# Tricorder-BoosterPack.net
KiCad netlist of a schematic drawn in EAGLE
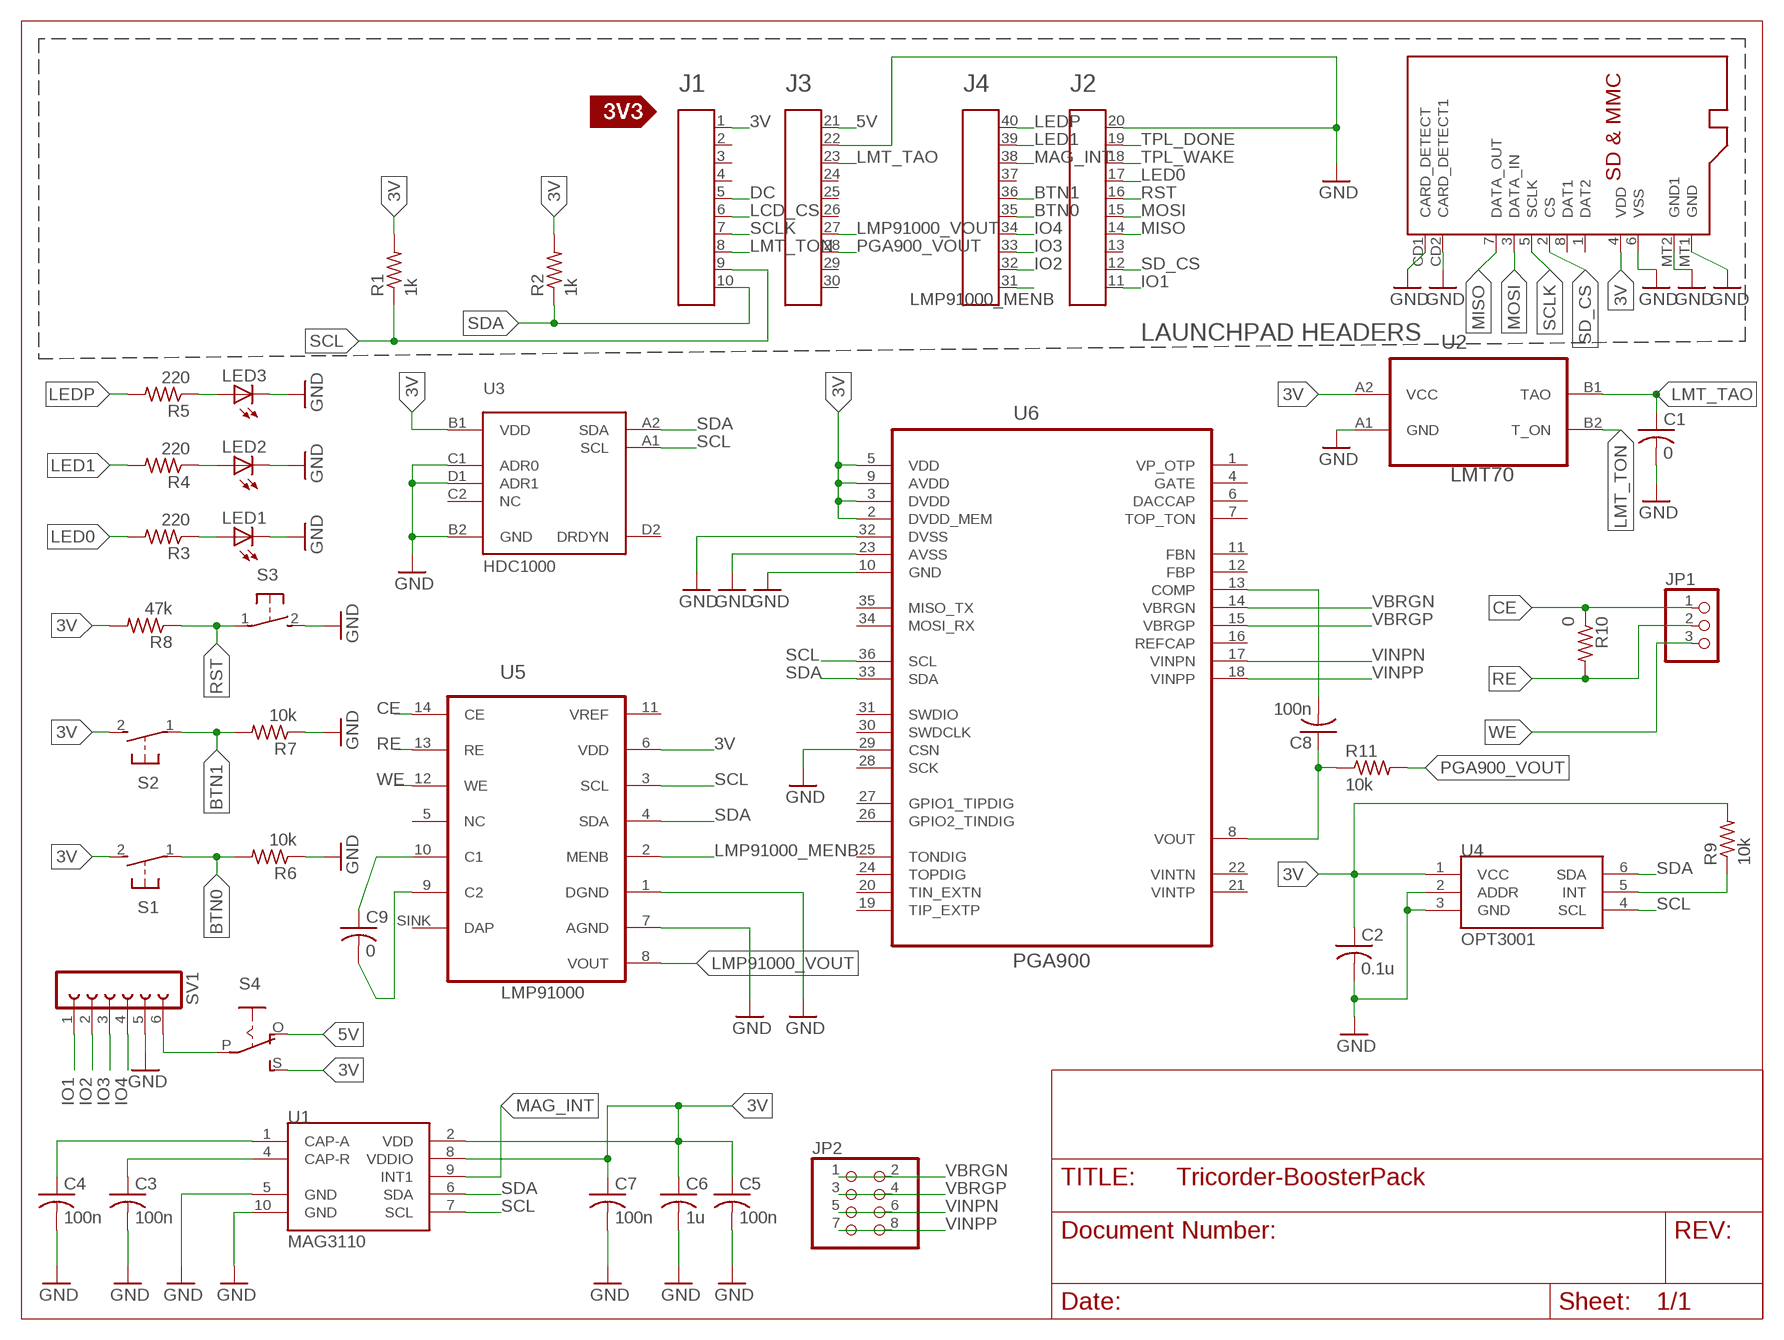
[diagram p0: schematic, sheet 1]

(export (version "E")
  (design (tool "Eeschema 10.0.6"))
  (components
    (comp (ref "A1")
      (value "HEADER4X10-BOOSTERPACK")
      (footprint "eagle-import:4X10-BOOSTERPACK")
      (libsource (lib "eagle-import") (part "HEADER4X10-BOOSTERPACK"))
    )
    (comp (ref "C1")
      (value "0")
      (footprint "eagle-import:C0603")
      (libsource (lib "eagle-import") (part "C-USC0603"))
    )
    (comp (ref "C2")
      (value "0.1u")
      (footprint "eagle-import:C0603")
      (libsource (lib "eagle-import") (part "C-USC0603"))
    )
    (comp (ref "C3")
      (value "100n")
      (footprint "eagle-import:C0603")
      (libsource (lib "eagle-import") (part "C-USC0603"))
    )
    (comp (ref "C4")
      (value "100n")
      (footprint "eagle-import:C0603")
      (libsource (lib "eagle-import") (part "C-USC0603"))
    )
    (comp (ref "C5")
      (value "100n")
      (footprint "eagle-import:C0603")
      (libsource (lib "eagle-import") (part "C-USC0603"))
    )
    (comp (ref "C6")
      (value "1u")
      (footprint "eagle-import:C0603")
      (libsource (lib "eagle-import") (part "C-USC0603"))
    )
    (comp (ref "C7")
      (value "100n")
      (footprint "eagle-import:C0603")
      (libsource (lib "eagle-import") (part "C-USC0603"))
    )
    (comp (ref "C8")
      (value "100n")
      (footprint "eagle-import:C0603")
      (libsource (lib "eagle-import") (part "C-USC0603"))
    )
    (comp (ref "C9")
      (value "0")
      (footprint "eagle-import:C0603")
      (libsource (lib "eagle-import") (part "C-USC0603"))
    )
    (comp (ref "JP1")
      (value "PINHD-1X3CB")
      (footprint "eagle-import:1X03-CLEANBIG")
      (libsource (lib "eagle-import") (part "PINHD-1X3CB"))
    )
    (comp (ref "JP2")
      (value "PINHD-2X4")
      (footprint "eagle-import:2X04")
      (libsource (lib "eagle-import") (part "PINHD-2X4"))
    )
    (comp (ref "LED1")
      (value "LEDCHIPLED_0603")
      (footprint "eagle-import:CHIPLED_0603")
      (libsource (lib "eagle-import") (part "LEDCHIPLED_0603"))
    )
    (comp (ref "LED2")
      (value "LEDCHIPLED_0603")
      (footprint "eagle-import:CHIPLED_0603")
      (libsource (lib "eagle-import") (part "LEDCHIPLED_0603"))
    )
    (comp (ref "LED3")
      (value "LEDCHIPLED_0603")
      (footprint "eagle-import:CHIPLED_0603")
      (libsource (lib "eagle-import") (part "LEDCHIPLED_0603"))
    )
    (comp (ref "R1")
      (value "1k")
      (footprint "eagle-import:R0603")
      (libsource (lib "eagle-import") (part "R-US_R0603"))
    )
    (comp (ref "R2")
      (value "1k")
      (footprint "eagle-import:R0603")
      (libsource (lib "eagle-import") (part "R-US_R0603"))
    )
    (comp (ref "R3")
      (value "220")
      (footprint "eagle-import:R0603")
      (libsource (lib "eagle-import") (part "R-US_R0603"))
    )
    (comp (ref "R4")
      (value "220")
      (footprint "eagle-import:R0603")
      (libsource (lib "eagle-import") (part "R-US_R0603"))
    )
    (comp (ref "R5")
      (value "220")
      (footprint "eagle-import:R0603")
      (libsource (lib "eagle-import") (part "R-US_R0603"))
    )
    (comp (ref "R6")
      (value "10k")
      (footprint "eagle-import:R0603")
      (libsource (lib "eagle-import") (part "R-US_R0603"))
    )
    (comp (ref "R7")
      (value "10k")
      (footprint "eagle-import:R0603")
      (libsource (lib "eagle-import") (part "R-US_R0603"))
    )
    (comp (ref "R8")
      (value "47k")
      (footprint "eagle-import:R0603")
      (libsource (lib "eagle-import") (part "R-US_R0603"))
    )
    (comp (ref "R9")
      (value "10k")
      (footprint "eagle-import:R0603")
      (libsource (lib "eagle-import") (part "R-US_R0603"))
    )
    (comp (ref "R10")
      (value "0")
      (footprint "eagle-import:R0603")
      (libsource (lib "eagle-import") (part "R-US_R0603"))
    )
    (comp (ref "R11")
      (value "10k")
      (footprint "eagle-import:R0603")
      (libsource (lib "eagle-import") (part "R-US_R0603"))
    )
    (comp (ref "S1")
      (value "31-XX")
      (footprint "eagle-import:B3F-31XX")
      (libsource (lib "eagle-import") (part "31-XX"))
    )
    (comp (ref "S2")
      (value "31-XX")
      (footprint "eagle-import:B3F-31XX")
      (libsource (lib "eagle-import") (part "31-XX"))
    )
    (comp (ref "S3")
      (value "31-XX")
      (footprint "eagle-import:B3F-31XX")
      (libsource (lib "eagle-import") (part "31-XX"))
    )
    (comp (ref "S4")
      (value "EG1218S")
      (footprint "eagle-import:EG1218")
      (libsource (lib "eagle-import") (part "EG1218S"))
    )
    (comp (ref "SV1")
      (value "FE06-1")
      (footprint "eagle-import:FE06")
      (libsource (lib "eagle-import") (part "FE06-1"))
    )
    (comp (ref "U$3")
      (value "SILK_3V3_TAG")
      (footprint "eagle-import:SILK_3V3_TAG")
      (libsource (lib "eagle-import") (part "SILK_3V3_TAG"))
    )
    (comp (ref "U1")
      (value "MAG3110")
      (footprint "eagle-import:DFN-10")
      (libsource (lib "eagle-import") (part "MAG3110"))
    )
    (comp (ref "U2")
      (value "LMT70LMT70")
      (footprint "eagle-import:BGA4C40P2X2_77X77X50")
      (fields (field (name "MPN") "LMT70"))
      (libsource (lib "eagle-import") (part "LMT70LMT70"))
    )
    (comp (ref "U3")
      (value "HDC1000")
      (footprint "eagle-import:DSBGA_8_YPA")
      (libsource (lib "eagle-import") (part "HDC1000"))
    )
    (comp (ref "U4")
      (value "OPT3001")
      (footprint "eagle-import:SOT23-6")
      (libsource (lib "eagle-import") (part "OPT3001"))
    )
    (comp (ref "U5")
      (value "LMP91000")
      (footprint "eagle-import:WFDFN-14")
      (fields (field (name "DIGIKEY") "LMP91000SDE/NOPBCT-ND") (field (name "DIGIKEY_1") "LMP91000"))
      (libsource (lib "eagle-import") (part "LMP91000"))
    )
    (comp (ref "U6")
      (value "PGA900")
      (footprint "eagle-import:QFN50P600X600X90-37N")
      (libsource (lib "eagle-import") (part "PGA900"))
    )
    (comp (ref "U7")
      (value "MICROSD")
      (footprint "eagle-import:MICROSD")
      (libsource (lib "eagle-import") (part "MICROSD"))
    )
  )
  (nets
    (net (code "1") (name "/DC") (class "Default")
      (node (ref "A1") (pin "5") (pinfunction "P$5_5") (pintype "bidirectional"))
    )
    (net (code "2") (name "/IO1") (class "Default")
      (node (ref "A1") (pin "11") (pinfunction "P$11_11") (pintype "bidirectional"))
      (node (ref "SV1") (pin "1") (pinfunction "1_1") (pintype "passive"))
    )
    (net (code "3") (name "/IO2") (class "Default")
      (node (ref "A1") (pin "32") (pinfunction "P$32_32") (pintype "bidirectional"))
      (node (ref "SV1") (pin "2") (pinfunction "2_2") (pintype "passive"))
    )
    (net (code "4") (name "/IO3") (class "Default")
      (node (ref "A1") (pin "33") (pinfunction "P$33_33") (pintype "bidirectional"))
      (node (ref "SV1") (pin "3") (pinfunction "3_3") (pintype "passive"))
    )
    (net (code "5") (name "/IO4") (class "Default")
      (node (ref "A1") (pin "34") (pinfunction "P$34_34") (pintype "bidirectional"))
      (node (ref "SV1") (pin "4") (pinfunction "4_4") (pintype "passive"))
    )
    (net (code "6") (name "/LCD_CS") (class "Default")
      (node (ref "A1") (pin "6") (pinfunction "P$6_6") (pintype "bidirectional"))
    )
    (net (code "7") (name "/LMP91000_MENB") (class "Default")
      (node (ref "A1") (pin "31") (pinfunction "P$31_31") (pintype "bidirectional"))
      (node (ref "U5") (pin "2") (pinfunction "MENB_2") (pintype "passive"))
    )
    (net (code "8") (name "/TPL_DONE") (class "Default")
      (node (ref "A1") (pin "19") (pinfunction "P$19_19") (pintype "bidirectional"))
    )
    (net (code "9") (name "/TPL_WAKE") (class "Default")
      (node (ref "A1") (pin "18") (pinfunction "P$18_18") (pintype "bidirectional"))
    )
    (net (code "10") (name "/VBRGN") (class "Default")
      (node (ref "JP2") (pin "1") (pinfunction "1_1") (pintype "passive"))
      (node (ref "JP2") (pin "2") (pinfunction "2_2") (pintype "passive"))
      (node (ref "U6") (pin "14") (pinfunction "VBRGN_14") (pintype "bidirectional"))
    )
    (net (code "11") (name "/VBRGP") (class "Default")
      (node (ref "JP2") (pin "3") (pinfunction "3_3") (pintype "passive"))
      (node (ref "JP2") (pin "4") (pinfunction "4_4") (pintype "passive"))
      (node (ref "U6") (pin "15") (pinfunction "VBRGP_15") (pintype "bidirectional"))
    )
    (net (code "12") (name "/VINPN") (class "Default")
      (node (ref "JP2") (pin "5") (pinfunction "5_5") (pintype "passive"))
      (node (ref "JP2") (pin "6") (pinfunction "6_6") (pintype "passive"))
      (node (ref "U6") (pin "17") (pinfunction "VINPN_17") (pintype "bidirectional"))
    )
    (net (code "13") (name "/VINPP") (class "Default")
      (node (ref "JP2") (pin "7") (pinfunction "7_7") (pintype "passive"))
      (node (ref "JP2") (pin "8") (pinfunction "8_8") (pintype "passive"))
      (node (ref "U6") (pin "18") (pinfunction "VINPP_18") (pintype "bidirectional"))
    )
    (net (code "14") (name "/VREF") (class "Default")
      (node (ref "U5") (pin "11") (pinfunction "VREF_11") (pintype "power_in"))
    )
    (net (code "15") (name "3V") (class "Default")
      (node (ref "A1") (pin "1") (pinfunction "P$1_1") (pintype "bidirectional"))
      (node (ref "C2") (pin "1") (pinfunction "1_1") (pintype "passive"))
      (node (ref "C5") (pin "1") (pinfunction "1_1") (pintype "passive"))
      (node (ref "C6") (pin "1") (pinfunction "1_1") (pintype "passive"))
      (node (ref "C7") (pin "1") (pinfunction "1_1") (pintype "passive"))
      (node (ref "R1") (pin "2") (pinfunction "2_2") (pintype "passive"))
      (node (ref "R2") (pin "2") (pinfunction "2_2") (pintype "passive"))
      (node (ref "R8") (pin "2") (pinfunction "2_2") (pintype "passive"))
      (node (ref "R9") (pin "2") (pinfunction "2_2") (pintype "passive"))
      (node (ref "S1") (pin "2") (pinfunction "S_2") (pintype "passive"))
      (node (ref "S2") (pin "2") (pinfunction "S_2") (pintype "passive"))
      (node (ref "S4") (pin "S") (pinfunction "S_S") (pintype "passive"))
      (node (ref "U1") (pin "2") (pinfunction "VDD_2") (pintype "bidirectional"))
      (node (ref "U1") (pin "8") (pinfunction "VDDIO_8") (pintype "bidirectional"))
      (node (ref "U3") (pin "B1") (pinfunction "VDD_B1") (pintype "power_in"))
      (node (ref "U4") (pin "1") (pinfunction "VCC_1") (pintype "power_in"))
      (node (ref "U5") (pin "6") (pinfunction "VDD_6") (pintype "power_in"))
      (node (ref "U6") (pin "2") (pinfunction "DVDD_MEM_2") (pintype "power_in"))
      (node (ref "U6") (pin "3") (pinfunction "DVDD_3") (pintype "power_in"))
      (node (ref "U6") (pin "5") (pinfunction "VDD_5") (pintype "power_in"))
      (node (ref "U6") (pin "9") (pinfunction "AVDD_9") (pintype "power_in"))
      (node (ref "U7") (pin "4") (pinfunction "VDD_4") (pintype "power_in"))
    )
    (net (code "16") (name "5V") (class "Default")
      (node (ref "A1") (pin "21") (pinfunction "P$21_21") (pintype "bidirectional"))
      (node (ref "S4") (pin "O") (pinfunction "O_O") (pintype "passive"))
    )
    (net (code "17") (name "BTN0") (class "Default")
      (node (ref "A1") (pin "35") (pinfunction "P$35_35") (pintype "bidirectional"))
      (node (ref "R6") (pin "2") (pinfunction "2_2") (pintype "passive"))
      (node (ref "S1") (pin "1") (pinfunction "P_1") (pintype "passive"))
    )
    (net (code "18") (name "BTN1") (class "Default")
      (node (ref "A1") (pin "36") (pinfunction "P$36_36") (pintype "bidirectional"))
      (node (ref "R7") (pin "2") (pinfunction "2_2") (pintype "passive"))
      (node (ref "S2") (pin "1") (pinfunction "P_1") (pintype "passive"))
    )
    (net (code "19") (name "CE") (class "Default")
      (node (ref "JP1") (pin "1") (pinfunction "1_1") (pintype "passive"))
      (node (ref "R10") (pin "1") (pinfunction "1_1") (pintype "passive"))
      (node (ref "U5") (pin "14") (pinfunction "CE_14") (pintype "bidirectional"))
    )
    (net (code "20") (name "GND") (class "Default")
      (node (ref "A1") (pin "20") (pinfunction "P$20_20") (pintype "bidirectional"))
      (node (ref "A1") (pin "22") (pinfunction "P$22_22") (pintype "bidirectional"))
      (node (ref "C1") (pin "2") (pinfunction "2_2") (pintype "passive"))
      (node (ref "C2") (pin "2") (pinfunction "2_2") (pintype "passive"))
      (node (ref "C3") (pin "2") (pinfunction "2_2") (pintype "passive"))
      (node (ref "C4") (pin "2") (pinfunction "2_2") (pintype "passive"))
      (node (ref "C5") (pin "2") (pinfunction "2_2") (pintype "passive"))
      (node (ref "C6") (pin "2") (pinfunction "2_2") (pintype "passive"))
      (node (ref "C7") (pin "2") (pinfunction "2_2") (pintype "passive"))
      (node (ref "LED1") (pin "C") (pinfunction "C_C") (pintype "passive"))
      (node (ref "LED2") (pin "C") (pinfunction "C_C") (pintype "passive"))
      (node (ref "LED3") (pin "C") (pinfunction "C_C") (pintype "passive"))
      (node (ref "R6") (pin "1") (pinfunction "1_1") (pintype "passive"))
      (node (ref "R7") (pin "1") (pinfunction "1_1") (pintype "passive"))
      (node (ref "S3") (pin "2") (pinfunction "S_2") (pintype "passive"))
      (node (ref "SV1") (pin "5") (pinfunction "5_5") (pintype "passive"))
      (node (ref "U1") (pin "10") (pinfunction "GND_10") (pintype "bidirectional"))
      (node (ref "U1") (pin "5") (pinfunction "GND_5") (pintype "bidirectional"))
      (node (ref "U2") (pin "A1") (pinfunction "GND_A1") (pintype "passive"))
      (node (ref "U3") (pin "B2") (pinfunction "GND_B2") (pintype "power_in"))
      (node (ref "U3") (pin "C1") (pinfunction "ADR0_C1") (pintype "input"))
      (node (ref "U3") (pin "D1") (pinfunction "ADR1_D1") (pintype "input"))
      (node (ref "U4") (pin "2") (pinfunction "ADDR_2") (pintype "input"))
      (node (ref "U4") (pin "3") (pinfunction "GND_3") (pintype "power_in"))
      (node (ref "U5") (pin "1") (pinfunction "DGND_1") (pintype "passive"))
      (node (ref "U5") (pin "7") (pinfunction "AGND_7") (pintype "passive"))
      (node (ref "U6") (pin "10") (pinfunction "GND_10") (pintype "power_in"))
      (node (ref "U6") (pin "23") (pinfunction "AVSS_23") (pintype "power_in"))
      (node (ref "U6") (pin "29") (pinfunction "CSN_29") (pintype "output"))
      (node (ref "U6") (pin "32") (pinfunction "DVSS_32") (pintype "power_in"))
      (node (ref "U7") (pin "6") (pinfunction "VSS_6") (pintype "power_in"))
      (node (ref "U7") (pin "CD1") (pinfunction "CARD_DETECT_CD1") (pintype "passive"))
      (node (ref "U7") (pin "CD2") (pinfunction "CARD_DETECT1_CD2") (pintype "passive"))
      (node (ref "U7") (pin "MT1") (pinfunction "GND_MT1") (pintype "power_in"))
      (node (ref "U7") (pin "MT2") (pinfunction "GND1_MT2") (pintype "power_in"))
    )
    (net (code "21") (name "LED0") (class "Default")
      (node (ref "A1") (pin "17") (pinfunction "P$17_17") (pintype "bidirectional"))
      (node (ref "R3") (pin "2") (pinfunction "2_2") (pintype "passive"))
    )
    (net (code "22") (name "LED1") (class "Default")
      (node (ref "A1") (pin "39") (pinfunction "P$39_39") (pintype "bidirectional"))
      (node (ref "R4") (pin "2") (pinfunction "2_2") (pintype "passive"))
    )
    (net (code "23") (name "LEDP") (class "Default")
      (node (ref "A1") (pin "40") (pinfunction "P$40_40") (pintype "bidirectional"))
      (node (ref "R5") (pin "2") (pinfunction "2_2") (pintype "passive"))
    )
    (net (code "24") (name "LMP91000_VOUT") (class "Default")
      (node (ref "A1") (pin "27") (pinfunction "P$27_27") (pintype "bidirectional"))
      (node (ref "U5") (pin "8") (pinfunction "VOUT_8") (pintype "passive"))
    )
    (net (code "25") (name "LMT_TAO") (class "Default")
      (node (ref "A1") (pin "23") (pinfunction "P$23_23") (pintype "bidirectional"))
      (node (ref "C1") (pin "1") (pinfunction "1_1") (pintype "passive"))
      (node (ref "U2") (pin "B1") (pinfunction "TAO_B1") (pintype "output"))
    )
    (net (code "26") (name "LMT_TON") (class "Default")
      (node (ref "A1") (pin "8") (pinfunction "P$8_8") (pintype "bidirectional"))
      (node (ref "U2") (pin "B2") (pinfunction "T_ON_B2") (pintype "input"))
    )
    (net (code "27") (name "MAG_INT") (class "Default")
      (node (ref "A1") (pin "38") (pinfunction "P$38_38") (pintype "bidirectional"))
      (node (ref "U1") (pin "9") (pinfunction "INT1_9") (pintype "bidirectional"))
    )
    (net (code "28") (name "MISO") (class "Default")
      (node (ref "A1") (pin "14") (pinfunction "P$14_14") (pintype "bidirectional"))
      (node (ref "U7") (pin "7") (pinfunction "DATA_OUT_7") (pintype "output"))
    )
    (net (code "29") (name "MOSI") (class "Default")
      (node (ref "A1") (pin "15") (pinfunction "P$15_15") (pintype "bidirectional"))
      (node (ref "U7") (pin "3") (pinfunction "DATA_IN_3") (pintype "input"))
    )
    (net (code "30") (name "Net-(LED1-PadA)") (class "Default")
      (node (ref "LED1") (pin "A") (pinfunction "A_A") (pintype "passive"))
      (node (ref "R3") (pin "1") (pinfunction "1_1") (pintype "passive"))
    )
    (net (code "31") (name "Net-(LED2-PadA)") (class "Default")
      (node (ref "LED2") (pin "A") (pinfunction "A_A") (pintype "passive"))
      (node (ref "R4") (pin "1") (pinfunction "1_1") (pintype "passive"))
    )
    (net (code "32") (name "Net-(LED3-PadA)") (class "Default")
      (node (ref "LED3") (pin "A") (pinfunction "A_A") (pintype "passive"))
      (node (ref "R5") (pin "1") (pinfunction "1_1") (pintype "passive"))
    )
    (net (code "33") (name "Net-(S4-PadP)") (class "Default")
      (node (ref "S4") (pin "P") (pinfunction "P_P") (pintype "passive"))
      (node (ref "SV1") (pin "6") (pinfunction "6_6") (pintype "passive"))
    )
    (net (code "34") (name "Net-(U1-CAP-A)") (class "Default")
      (node (ref "C4") (pin "1") (pinfunction "1_1") (pintype "passive"))
      (node (ref "U1") (pin "1") (pinfunction "CAP-A_1") (pintype "bidirectional"))
    )
    (net (code "35") (name "Net-(U1-CAP-R)") (class "Default")
      (node (ref "C3") (pin "1") (pinfunction "1_1") (pintype "passive"))
      (node (ref "U1") (pin "4") (pinfunction "CAP-R_4") (pintype "bidirectional"))
    )
    (net (code "36") (name "Net-(U4-INT)") (class "Default")
      (node (ref "R9") (pin "1") (pinfunction "1_1") (pintype "passive"))
      (node (ref "U4") (pin "5") (pinfunction "INT_5") (pintype "output"))
    )
    (net (code "37") (name "Net-(U5-C1)") (class "Default")
      (node (ref "C9") (pin "1") (pinfunction "1_1") (pintype "passive"))
      (node (ref "U5") (pin "10") (pinfunction "C1_10") (pintype "passive"))
    )
    (net (code "38") (name "Net-(U5-C2)") (class "Default")
      (node (ref "C9") (pin "2") (pinfunction "2_2") (pintype "passive"))
      (node (ref "U5") (pin "9") (pinfunction "C2_9") (pintype "passive"))
    )
    (net (code "39") (name "Net-(U6-COMP)") (class "Default")
      (node (ref "C8") (pin "2") (pinfunction "2_2") (pintype "passive"))
      (node (ref "U6") (pin "13") (pinfunction "COMP_13") (pintype "bidirectional"))
    )
    (net (code "40") (name "Net-(U6-VOUT)") (class "Default")
      (node (ref "C8") (pin "1") (pinfunction "1_1") (pintype "passive"))
      (node (ref "R11") (pin "1") (pinfunction "1_1") (pintype "passive"))
      (node (ref "U6") (pin "8") (pinfunction "VOUT_8") (pintype "bidirectional"))
    )
    (net (code "41") (name "PGA900_VOUT") (class "Default")
      (node (ref "A1") (pin "28") (pinfunction "P$28_28") (pintype "bidirectional"))
      (node (ref "R11") (pin "2") (pinfunction "2_2") (pintype "passive"))
    )
    (net (code "42") (name "RE") (class "Default")
      (node (ref "JP1") (pin "2") (pinfunction "2_2") (pintype "passive"))
      (node (ref "R10") (pin "2") (pinfunction "2_2") (pintype "passive"))
      (node (ref "U5") (pin "13") (pinfunction "RE_13") (pintype "bidirectional"))
    )
    (net (code "43") (name "RST") (class "Default")
      (node (ref "A1") (pin "16") (pinfunction "P$16_16") (pintype "bidirectional"))
      (node (ref "R8") (pin "1") (pinfunction "1_1") (pintype "passive"))
      (node (ref "S3") (pin "1") (pinfunction "P_1") (pintype "passive"))
    )
    (net (code "44") (name "SCL") (class "Default")
      (node (ref "A1") (pin "9") (pinfunction "P$9_9") (pintype "bidirectional"))
      (node (ref "R1") (pin "1") (pinfunction "1_1") (pintype "passive"))
      (node (ref "U1") (pin "7") (pinfunction "SCL_7") (pintype "bidirectional"))
      (node (ref "U3") (pin "A1") (pinfunction "SCL_A1") (pintype "input"))
      (node (ref "U4") (pin "4") (pinfunction "SCL_4") (pintype "input"))
      (node (ref "U5") (pin "3") (pinfunction "SCL_3") (pintype "bidirectional"))
      (node (ref "U6") (pin "36") (pinfunction "SCL_36") (pintype "bidirectional"))
    )
    (net (code "45") (name "SCLK") (class "Default")
      (node (ref "A1") (pin "7") (pinfunction "P$7_7") (pintype "bidirectional"))
      (node (ref "U7") (pin "5") (pinfunction "SCLK_5") (pintype "input"))
    )
    (net (code "46") (name "SDA") (class "Default")
      (node (ref "A1") (pin "10") (pinfunction "P$10_10") (pintype "bidirectional"))
      (node (ref "R2") (pin "1") (pinfunction "1_1") (pintype "passive"))
      (node (ref "U1") (pin "6") (pinfunction "SDA_6") (pintype "bidirectional"))
      (node (ref "U3") (pin "A2") (pinfunction "SDA_A2") (pintype "bidirectional"))
      (node (ref "U4") (pin "6") (pinfunction "SDA_6") (pintype "input"))
      (node (ref "U5") (pin "4") (pinfunction "SDA_4") (pintype "passive"))
      (node (ref "U6") (pin "33") (pinfunction "SDA_33") (pintype "bidirectional"))
    )
    (net (code "47") (name "SD_CS") (class "Default")
      (node (ref "A1") (pin "12") (pinfunction "P$12_12") (pintype "bidirectional"))
      (node (ref "U7") (pin "2") (pinfunction "CS_2") (pintype "input"))
    )
    (net (code "48") (name "WE") (class "Default")
      (node (ref "JP1") (pin "3") (pinfunction "3_3") (pintype "passive"))
      (node (ref "U5") (pin "12") (pinfunction "WE_12") (pintype "bidirectional"))
    )
    (net (code "49") (name "unconnected-(A1-P$2-Pad2)") (class "Default")
      (node (ref "A1") (pin "2") (pinfunction "P$2_2") (pintype "bidirectional"))
    )
    (net (code "50") (name "unconnected-(A1-P$3-Pad3)") (class "Default")
      (node (ref "A1") (pin "3") (pinfunction "P$3_3") (pintype "bidirectional"))
    )
    (net (code "51") (name "unconnected-(A1-P$4-Pad4)") (class "Default")
      (node (ref "A1") (pin "4") (pinfunction "P$4_4") (pintype "bidirectional"))
    )
    (net (code "52") (name "unconnected-(A1-P$13-Pad13)") (class "Default")
      (node (ref "A1") (pin "13") (pinfunction "P$13_13") (pintype "bidirectional"))
    )
    (net (code "53") (name "unconnected-(A1-P$24-Pad24)") (class "Default")
      (node (ref "A1") (pin "24") (pinfunction "P$24_24") (pintype "bidirectional"))
    )
    (net (code "54") (name "unconnected-(A1-P$25-Pad25)") (class "Default")
      (node (ref "A1") (pin "25") (pinfunction "P$25_25") (pintype "bidirectional"))
    )
    (net (code "55") (name "unconnected-(A1-P$26-Pad26)") (class "Default")
      (node (ref "A1") (pin "26") (pinfunction "P$26_26") (pintype "bidirectional"))
    )
    (net (code "56") (name "unconnected-(A1-P$29-Pad29)") (class "Default")
      (node (ref "A1") (pin "29") (pinfunction "P$29_29") (pintype "bidirectional"))
    )
    (net (code "57") (name "unconnected-(A1-P$30-Pad30)") (class "Default")
      (node (ref "A1") (pin "30") (pinfunction "P$30_30") (pintype "bidirectional"))
    )
    (net (code "58") (name "unconnected-(A1-P$37-Pad37)") (class "Default")
      (node (ref "A1") (pin "37") (pinfunction "P$37_37") (pintype "bidirectional"))
    )
    (net (code "59") (name "unconnected-(U2-VCC-PadA2)") (class "Default")
      (node (ref "U2") (pin "A2") (pinfunction "VCC_A2") (pintype "power_in"))
    )
    (net (code "60") (name "unconnected-(U3-DRDYN-PadD2)") (class "Default")
      (node (ref "U3") (pin "D2") (pinfunction "DRDYN_D2") (pintype "output"))
    )
    (net (code "61") (name "unconnected-(U3-NC-PadC2)") (class "Default")
      (node (ref "U3") (pin "C2") (pinfunction "NC_C2") (pintype "no_connect"))
    )
    (net (code "62") (name "unconnected-(U5-DAP-PadSINK)") (class "Default")
      (node (ref "U5") (pin "SINK") (pinfunction "DAP_SINK") (pintype "passive"))
    )
    (net (code "63") (name "unconnected-(U5-NC-Pad5)") (class "Default")
      (node (ref "U5") (pin "5") (pinfunction "NC_5") (pintype "passive"))
    )
    (net (code "64") (name "unconnected-(U6-DACCAP-Pad6)") (class "Default")
      (node (ref "U6") (pin "6") (pinfunction "DACCAP_6") (pintype "bidirectional"))
    )
    (net (code "65") (name "unconnected-(U6-FBN-Pad11)") (class "Default")
      (node (ref "U6") (pin "11") (pinfunction "FBN_11") (pintype "bidirectional"))
    )
    (net (code "66") (name "unconnected-(U6-FBP-Pad12)") (class "Default")
      (node (ref "U6") (pin "12") (pinfunction "FBP_12") (pintype "bidirectional"))
    )
    (net (code "67") (name "unconnected-(U6-GATE-Pad4)") (class "Default")
      (node (ref "U6") (pin "4") (pinfunction "GATE_4") (pintype "bidirectional"))
    )
    (net (code "68") (name "unconnected-(U6-GPIO1_TIPDIG-Pad27)") (class "Default")
      (node (ref "U6") (pin "27") (pinfunction "GPIO1_TIPDIG_27") (pintype "bidirectional"))
    )
    (net (code "69") (name "unconnected-(U6-GPIO2_TINDIG-Pad26)") (class "Default")
      (node (ref "U6") (pin "26") (pinfunction "GPIO2_TINDIG_26") (pintype "bidirectional"))
    )
    (net (code "70") (name "unconnected-(U6-MISO_TX-Pad35)") (class "Default")
      (node (ref "U6") (pin "35") (pinfunction "MISO_TX_35") (pintype "output"))
    )
    (net (code "71") (name "unconnected-(U6-MOSI_RX-Pad34)") (class "Default")
      (node (ref "U6") (pin "34") (pinfunction "MOSI_RX_34") (pintype "input"))
    )
    (net (code "72") (name "unconnected-(U6-REFCAP-Pad16)") (class "Default")
      (node (ref "U6") (pin "16") (pinfunction "REFCAP_16") (pintype "bidirectional"))
    )
    (net (code "73") (name "unconnected-(U6-SCK-Pad28)") (class "Default")
      (node (ref "U6") (pin "28") (pinfunction "SCK_28") (pintype "output"))
    )
    (net (code "74") (name "unconnected-(U6-SWDCLK-Pad30)") (class "Default")
      (node (ref "U6") (pin "30") (pinfunction "SWDCLK_30") (pintype "bidirectional"))
    )
    (net (code "75") (name "unconnected-(U6-SWDIO-Pad31)") (class "Default")
      (node (ref "U6") (pin "31") (pinfunction "SWDIO_31") (pintype "bidirectional"))
    )
    (net (code "76") (name "unconnected-(U6-TIN_EXTN-Pad20)") (class "Default")
      (node (ref "U6") (pin "20") (pinfunction "TIN_EXTN_20") (pintype "input"))
    )
    (net (code "77") (name "unconnected-(U6-TIP_EXTP-Pad19)") (class "Default")
      (node (ref "U6") (pin "19") (pinfunction "TIP_EXTP_19") (pintype "input"))
    )
    (net (code "78") (name "unconnected-(U6-TONDIG-Pad25)") (class "Default")
      (node (ref "U6") (pin "25") (pinfunction "TONDIG_25") (pintype "output"))
    )
    (net (code "79") (name "unconnected-(U6-TOPDIG-Pad24)") (class "Default")
      (node (ref "U6") (pin "24") (pinfunction "TOPDIG_24") (pintype "output"))
    )
    (net (code "80") (name "unconnected-(U6-TOP_TON-Pad7)") (class "Default")
      (node (ref "U6") (pin "7") (pinfunction "TOP_TON_7") (pintype "bidirectional"))
    )
    (net (code "81") (name "unconnected-(U6-VINTN-Pad22)") (class "Default")
      (node (ref "U6") (pin "22") (pinfunction "VINTN_22") (pintype "input"))
    )
    (net (code "82") (name "unconnected-(U6-VINTP-Pad21)") (class "Default")
      (node (ref "U6") (pin "21") (pinfunction "VINTP_21") (pintype "bidirectional"))
    )
    (net (code "83") (name "unconnected-(U6-VP_OTP-Pad1)") (class "Default")
      (node (ref "U6") (pin "1") (pinfunction "VP_OTP_1") (pintype "bidirectional"))
    )
    (net (code "84") (name "unconnected-(U7-DAT1-Pad8)") (class "Default")
      (node (ref "U7") (pin "8") (pinfunction "DAT1_8") (pintype "bidirectional"))
    )
    (net (code "85") (name "unconnected-(U7-DAT2-Pad1)") (class "Default")
      (node (ref "U7") (pin "1") (pinfunction "DAT2_1") (pintype "bidirectional"))
    )
  )
)
